# MAX3462.net
KiCad netlist of a schematic drawn in Altium Designer
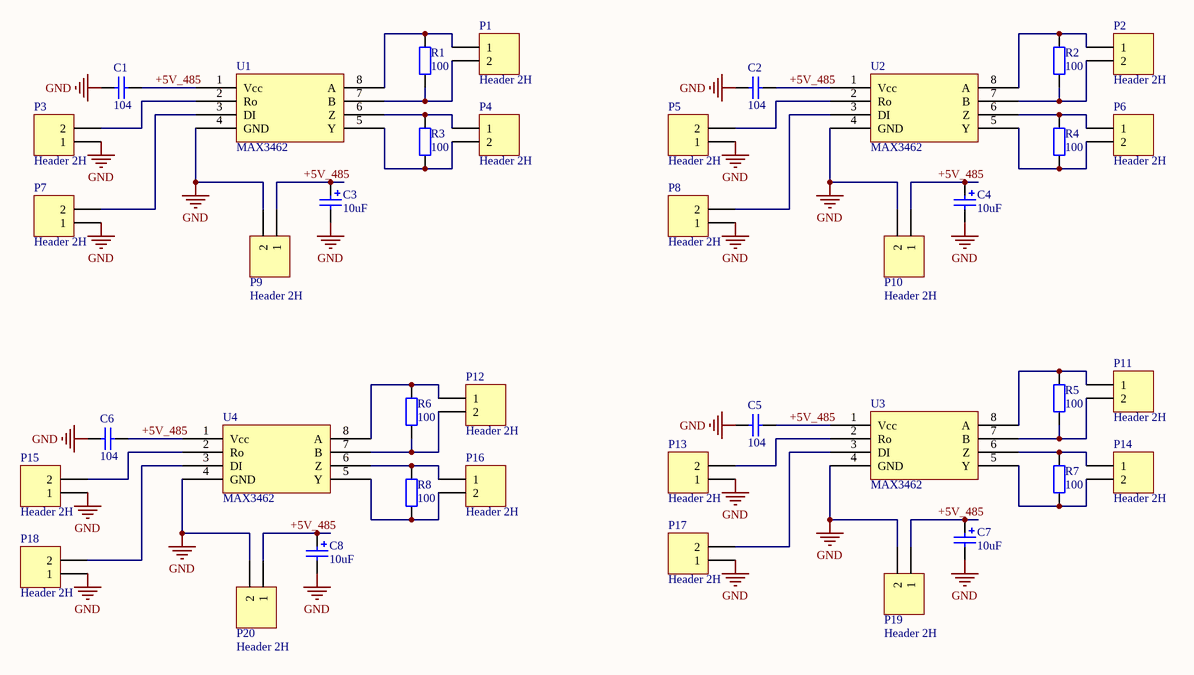
[diagram p0: MAX3462.SchDoc]

(export (version "E")
  (design (tool "Eeschema 10.0.6"))
  (components
    (comp (ref "C1")
      (value "104")
      (footprint "0805C")
      (description "Capacitor")
      (fields (field (name "PUBLISHER") "Altium Limited"))
      (libsource (lib "Miscellaneous Devices") (part "Cap"))
    )
    (comp (ref "C2")
      (value "104")
      (footprint "0805C")
      (description "Capacitor")
      (fields (field (name "PUBLISHER") "Altium Limited"))
      (libsource (lib "Miscellaneous Devices") (part "Cap"))
    )
    (comp (ref "C3")
      (value "10uF")
      (footprint "C68uF")
      (description "Polarized Capacitor (Axial)")
      (fields (field (name "PUBLISHER") "Altium Limited"))
      (libsource (lib "Miscellaneous Devices") (part "Cap Pol2"))
    )
    (comp (ref "C4")
      (value "10uF")
      (footprint "C68uF")
      (description "Polarized Capacitor (Axial)")
      (fields (field (name "PUBLISHER") "Altium Limited"))
      (libsource (lib "Miscellaneous Devices") (part "Cap Pol2"))
    )
    (comp (ref "C5")
      (value "104")
      (footprint "0805C")
      (description "Capacitor")
      (fields (field (name "PUBLISHER") "Altium Limited"))
      (libsource (lib "Miscellaneous Devices") (part "Cap"))
    )
    (comp (ref "C6")
      (value "104")
      (footprint "0805C")
      (description "Capacitor")
      (fields (field (name "PUBLISHER") "Altium Limited"))
      (libsource (lib "Miscellaneous Devices") (part "Cap"))
    )
    (comp (ref "C7")
      (value "10uF")
      (footprint "C68uF")
      (description "Polarized Capacitor (Axial)")
      (fields (field (name "PUBLISHER") "Altium Limited"))
      (libsource (lib "Miscellaneous Devices") (part "Cap Pol2"))
    )
    (comp (ref "C8")
      (value "10uF")
      (footprint "C68uF")
      (description "Polarized Capacitor (Axial)")
      (fields (field (name "PUBLISHER") "Altium Limited"))
      (libsource (lib "Miscellaneous Devices") (part "Cap Pol2"))
    )
    (comp (ref "P1")
      (value "Header 2H")
      (footprint "HDR1X2")
      (description "Header, 2-Pin, Right Angle")
      (fields (field (name "PUBLISHER") "Altium Limited"))
      (libsource (lib "Miscellaneous Connectors") (part "Header 2H"))
    )
    (comp (ref "P2")
      (value "Header 2H")
      (footprint "HDR1X2")
      (description "Header, 2-Pin, Right Angle")
      (fields (field (name "PUBLISHER") "Altium Limited"))
      (libsource (lib "Miscellaneous Connectors") (part "Header 2H"))
    )
    (comp (ref "P3")
      (value "Header 2H")
      (footprint "HDR1X2")
      (description "Header, 2-Pin, Right Angle")
      (fields (field (name "PUBLISHER") "Altium Limited"))
      (libsource (lib "") (part "Header 2H_2"))
    )
    (comp (ref "P4")
      (value "Header 2H")
      (footprint "HDR1X2")
      (description "Header, 2-Pin, Right Angle")
      (fields (field (name "PUBLISHER") "Altium Limited"))
      (libsource (lib "Miscellaneous Connectors") (part "Header 2H"))
    )
    (comp (ref "P5")
      (value "Header 2H")
      (footprint "HDR1X2")
      (description "Header, 2-Pin, Right Angle")
      (fields (field (name "PUBLISHER") "Altium Limited"))
      (libsource (lib "") (part "Header 2H_2"))
    )
    (comp (ref "P6")
      (value "Header 2H")
      (footprint "HDR1X2")
      (description "Header, 2-Pin, Right Angle")
      (fields (field (name "PUBLISHER") "Altium Limited"))
      (libsource (lib "Miscellaneous Connectors") (part "Header 2H"))
    )
    (comp (ref "P7")
      (value "Header 2H")
      (footprint "HDR1X2")
      (description "Header, 2-Pin, Right Angle")
      (fields (field (name "PUBLISHER") "Altium Limited"))
      (libsource (lib "") (part "Header 2H_2"))
    )
    (comp (ref "P8")
      (value "Header 2H")
      (footprint "HDR1X2")
      (description "Header, 2-Pin, Right Angle")
      (fields (field (name "PUBLISHER") "Altium Limited"))
      (libsource (lib "") (part "Header 2H_2"))
    )
    (comp (ref "P9")
      (value "Header 2H")
      (footprint "HDR1X2")
      (description "Header, 2-Pin, Right Angle")
      (fields (field (name "PUBLISHER") "Altium Limited"))
      (libsource (lib "") (part "Header 2H_1"))
    )
    (comp (ref "P10")
      (value "Header 2H")
      (footprint "HDR1X2")
      (description "Header, 2-Pin, Right Angle")
      (fields (field (name "PUBLISHER") "Altium Limited"))
      (libsource (lib "") (part "Header 2H_1"))
    )
    (comp (ref "P11")
      (value "Header 2H")
      (footprint "HDR1X2")
      (description "Header, 2-Pin, Right Angle")
      (fields (field (name "PUBLISHER") "Altium Limited"))
      (libsource (lib "Miscellaneous Connectors") (part "Header 2H"))
    )
    (comp (ref "P12")
      (value "Header 2H")
      (footprint "HDR1X2")
      (description "Header, 2-Pin, Right Angle")
      (fields (field (name "PUBLISHER") "Altium Limited"))
      (libsource (lib "Miscellaneous Connectors") (part "Header 2H"))
    )
    (comp (ref "P13")
      (value "Header 2H")
      (footprint "HDR1X2")
      (description "Header, 2-Pin, Right Angle")
      (fields (field (name "PUBLISHER") "Altium Limited"))
      (libsource (lib "") (part "Header 2H_2"))
    )
    (comp (ref "P14")
      (value "Header 2H")
      (footprint "HDR1X2")
      (description "Header, 2-Pin, Right Angle")
      (fields (field (name "PUBLISHER") "Altium Limited"))
      (libsource (lib "Miscellaneous Connectors") (part "Header 2H"))
    )
    (comp (ref "P15")
      (value "Header 2H")
      (footprint "HDR1X2")
      (description "Header, 2-Pin, Right Angle")
      (fields (field (name "PUBLISHER") "Altium Limited"))
      (libsource (lib "") (part "Header 2H_2"))
    )
    (comp (ref "P16")
      (value "Header 2H")
      (footprint "HDR1X2")
      (description "Header, 2-Pin, Right Angle")
      (fields (field (name "PUBLISHER") "Altium Limited"))
      (libsource (lib "Miscellaneous Connectors") (part "Header 2H"))
    )
    (comp (ref "P17")
      (value "Header 2H")
      (footprint "HDR1X2")
      (description "Header, 2-Pin, Right Angle")
      (fields (field (name "PUBLISHER") "Altium Limited"))
      (libsource (lib "") (part "Header 2H_2"))
    )
    (comp (ref "P18")
      (value "Header 2H")
      (footprint "HDR1X2")
      (description "Header, 2-Pin, Right Angle")
      (fields (field (name "PUBLISHER") "Altium Limited"))
      (libsource (lib "") (part "Header 2H_2"))
    )
    (comp (ref "P19")
      (value "Header 2H")
      (footprint "HDR1X2")
      (description "Header, 2-Pin, Right Angle")
      (fields (field (name "PUBLISHER") "Altium Limited"))
      (libsource (lib "") (part "Header 2H_1"))
    )
    (comp (ref "P20")
      (value "Header 2H")
      (footprint "HDR1X2")
      (description "Header, 2-Pin, Right Angle")
      (fields (field (name "PUBLISHER") "Altium Limited"))
      (libsource (lib "") (part "Header 2H_1"))
    )
    (comp (ref "R1")
      (value "100")
      (footprint "0805R")
      (description "Resistor")
      (fields (field (name "PUBLISHER") "Altium Limited"))
      (libsource (lib "Miscellaneous Devices") (part "Res2"))
    )
    (comp (ref "R2")
      (value "100")
      (footprint "0805R")
      (description "Resistor")
      (fields (field (name "PUBLISHER") "Altium Limited"))
      (libsource (lib "Miscellaneous Devices") (part "Res2"))
    )
    (comp (ref "R3")
      (value "100")
      (footprint "0805R")
      (description "Resistor")
      (fields (field (name "PUBLISHER") "Altium Limited"))
      (libsource (lib "Miscellaneous Devices") (part "Res2"))
    )
    (comp (ref "R4")
      (value "100")
      (footprint "0805R")
      (description "Resistor")
      (fields (field (name "PUBLISHER") "Altium Limited"))
      (libsource (lib "Miscellaneous Devices") (part "Res2"))
    )
    (comp (ref "R5")
      (value "100")
      (footprint "0805R")
      (description "Resistor")
      (fields (field (name "PUBLISHER") "Altium Limited"))
      (libsource (lib "Miscellaneous Devices") (part "Res2"))
    )
    (comp (ref "R6")
      (value "100")
      (footprint "0805R")
      (description "Resistor")
      (fields (field (name "PUBLISHER") "Altium Limited"))
      (libsource (lib "Miscellaneous Devices") (part "Res2"))
    )
    (comp (ref "R7")
      (value "100")
      (footprint "0805R")
      (description "Resistor")
      (fields (field (name "PUBLISHER") "Altium Limited"))
      (libsource (lib "Miscellaneous Devices") (part "Res2"))
    )
    (comp (ref "R8")
      (value "100")
      (footprint "0805R")
      (description "Resistor")
      (fields (field (name "PUBLISHER") "Altium Limited"))
      (libsource (lib "Miscellaneous Devices") (part "Res2"))
    )
    (comp (ref "U1") (value "MAX3462") (footprint "SO8") (libsource (lib "Schlib1") (part "MAX3462")))
    (comp (ref "U2") (value "MAX3462") (footprint "SO8") (libsource (lib "Schlib1") (part "MAX3462")))
    (comp (ref "U3") (value "MAX3462") (footprint "SO8") (libsource (lib "Schlib1") (part "MAX3462")))
    (comp (ref "U4") (value "MAX3462") (footprint "SO8") (libsource (lib "Schlib1") (part "MAX3462")))
  )
  (nets
    (net (code "1") (name "/+5V_485") (class "Default")
      (node (ref "C1") (pin "2") (pinfunction "2_2") (pintype "passive"))
      (node (ref "C2") (pin "2") (pinfunction "2_2") (pintype "passive"))
      (node (ref "C3") (pin "1") (pinfunction "1_1") (pintype "passive"))
      (node (ref "C4") (pin "1") (pinfunction "1_1") (pintype "passive"))
      (node (ref "C5") (pin "2") (pinfunction "2_2") (pintype "passive"))
      (node (ref "C6") (pin "2") (pinfunction "2_2") (pintype "passive"))
      (node (ref "C7") (pin "1") (pinfunction "1_1") (pintype "passive"))
      (node (ref "C8") (pin "1") (pinfunction "1_1") (pintype "passive"))
      (node (ref "P10") (pin "1") (pinfunction "1_1") (pintype "passive"))
      (node (ref "P19") (pin "1") (pinfunction "1_1") (pintype "passive"))
      (node (ref "P20") (pin "1") (pinfunction "1_1") (pintype "passive"))
      (node (ref "P9") (pin "1") (pinfunction "1_1") (pintype "passive"))
      (node (ref "U1") (pin "1") (pinfunction "Vcc_1") (pintype "passive"))
      (node (ref "U2") (pin "1") (pinfunction "Vcc_1") (pintype "passive"))
      (node (ref "U3") (pin "1") (pinfunction "Vcc_1") (pintype "passive"))
      (node (ref "U4") (pin "1") (pinfunction "Vcc_1") (pintype "passive"))
    )
    (net (code "2") (name "GND") (class "Default")
      (node (ref "C1") (pin "1") (pinfunction "1_1") (pintype "passive"))
      (node (ref "C2") (pin "1") (pinfunction "1_1") (pintype "passive"))
      (node (ref "C3") (pin "2") (pinfunction "2_2") (pintype "passive"))
      (node (ref "C4") (pin "2") (pinfunction "2_2") (pintype "passive"))
      (node (ref "C5") (pin "1") (pinfunction "1_1") (pintype "passive"))
      (node (ref "C6") (pin "1") (pinfunction "1_1") (pintype "passive"))
      (node (ref "C7") (pin "2") (pinfunction "2_2") (pintype "passive"))
      (node (ref "C8") (pin "2") (pinfunction "2_2") (pintype "passive"))
      (node (ref "P10") (pin "2") (pinfunction "2_2") (pintype "passive"))
      (node (ref "P13") (pin "1") (pinfunction "1_1") (pintype "passive"))
      (node (ref "P15") (pin "1") (pinfunction "1_1") (pintype "passive"))
      (node (ref "P17") (pin "1") (pinfunction "1_1") (pintype "passive"))
      (node (ref "P18") (pin "1") (pinfunction "1_1") (pintype "passive"))
      (node (ref "P19") (pin "2") (pinfunction "2_2") (pintype "passive"))
      (node (ref "P20") (pin "2") (pinfunction "2_2") (pintype "passive"))
      (node (ref "P3") (pin "1") (pinfunction "1_1") (pintype "passive"))
      (node (ref "P5") (pin "1") (pinfunction "1_1") (pintype "passive"))
      (node (ref "P7") (pin "1") (pinfunction "1_1") (pintype "passive"))
      (node (ref "P8") (pin "1") (pinfunction "1_1") (pintype "passive"))
      (node (ref "P9") (pin "2") (pinfunction "2_2") (pintype "passive"))
      (node (ref "U1") (pin "4") (pinfunction "GND_4") (pintype "passive"))
      (node (ref "U2") (pin "4") (pinfunction "GND_4") (pintype "passive"))
      (node (ref "U3") (pin "4") (pinfunction "GND_4") (pintype "passive"))
      (node (ref "U4") (pin "4") (pinfunction "GND_4") (pintype "passive"))
    )
    (net (code "3") (name "Net-(U1-A)") (class "Default")
      (node (ref "P1") (pin "1") (pinfunction "1_1") (pintype "passive"))
      (node (ref "R1") (pin "2") (pinfunction "2_2") (pintype "passive"))
      (node (ref "U1") (pin "8") (pinfunction "A_8") (pintype "passive"))
    )
    (net (code "4") (name "Net-(U1-B)") (class "Default")
      (node (ref "P1") (pin "2") (pinfunction "2_2") (pintype "passive"))
      (node (ref "R1") (pin "1") (pinfunction "1_1") (pintype "passive"))
      (node (ref "U1") (pin "7") (pinfunction "B_7") (pintype "passive"))
    )
    (net (code "5") (name "Net-(U1-DI)") (class "Default")
      (node (ref "P7") (pin "2") (pinfunction "2_2") (pintype "passive"))
      (node (ref "U1") (pin "3") (pinfunction "DI_3") (pintype "passive"))
    )
    (net (code "6") (name "Net-(U1-Ro)") (class "Default")
      (node (ref "P3") (pin "2") (pinfunction "2_2") (pintype "passive"))
      (node (ref "U1") (pin "2") (pinfunction "Ro_2") (pintype "passive"))
    )
    (net (code "7") (name "Net-(U1-Y)") (class "Default")
      (node (ref "P4") (pin "2") (pinfunction "2_2") (pintype "passive"))
      (node (ref "R3") (pin "1") (pinfunction "1_1") (pintype "passive"))
      (node (ref "U1") (pin "5") (pinfunction "Y_5") (pintype "passive"))
    )
    (net (code "8") (name "Net-(U1-Z)") (class "Default")
      (node (ref "P4") (pin "1") (pinfunction "1_1") (pintype "passive"))
      (node (ref "R3") (pin "2") (pinfunction "2_2") (pintype "passive"))
      (node (ref "U1") (pin "6") (pinfunction "Z_6") (pintype "passive"))
    )
    (net (code "9") (name "Net-(U2-A)") (class "Default")
      (node (ref "P2") (pin "1") (pinfunction "1_1") (pintype "passive"))
      (node (ref "R2") (pin "2") (pinfunction "2_2") (pintype "passive"))
      (node (ref "U2") (pin "8") (pinfunction "A_8") (pintype "passive"))
    )
    (net (code "10") (name "Net-(U2-B)") (class "Default")
      (node (ref "P2") (pin "2") (pinfunction "2_2") (pintype "passive"))
      (node (ref "R2") (pin "1") (pinfunction "1_1") (pintype "passive"))
      (node (ref "U2") (pin "7") (pinfunction "B_7") (pintype "passive"))
    )
    (net (code "11") (name "Net-(U2-DI)") (class "Default")
      (node (ref "P8") (pin "2") (pinfunction "2_2") (pintype "passive"))
      (node (ref "U2") (pin "3") (pinfunction "DI_3") (pintype "passive"))
    )
    (net (code "12") (name "Net-(U2-Ro)") (class "Default")
      (node (ref "P5") (pin "2") (pinfunction "2_2") (pintype "passive"))
      (node (ref "U2") (pin "2") (pinfunction "Ro_2") (pintype "passive"))
    )
    (net (code "13") (name "Net-(U2-Y)") (class "Default")
      (node (ref "P6") (pin "2") (pinfunction "2_2") (pintype "passive"))
      (node (ref "R4") (pin "1") (pinfunction "1_1") (pintype "passive"))
      (node (ref "U2") (pin "5") (pinfunction "Y_5") (pintype "passive"))
    )
    (net (code "14") (name "Net-(U2-Z)") (class "Default")
      (node (ref "P6") (pin "1") (pinfunction "1_1") (pintype "passive"))
      (node (ref "R4") (pin "2") (pinfunction "2_2") (pintype "passive"))
      (node (ref "U2") (pin "6") (pinfunction "Z_6") (pintype "passive"))
    )
    (net (code "15") (name "Net-(U3-A)") (class "Default")
      (node (ref "P11") (pin "1") (pinfunction "1_1") (pintype "passive"))
      (node (ref "R5") (pin "2") (pinfunction "2_2") (pintype "passive"))
      (node (ref "U3") (pin "8") (pinfunction "A_8") (pintype "passive"))
    )
    (net (code "16") (name "Net-(U3-B)") (class "Default")
      (node (ref "P11") (pin "2") (pinfunction "2_2") (pintype "passive"))
      (node (ref "R5") (pin "1") (pinfunction "1_1") (pintype "passive"))
      (node (ref "U3") (pin "7") (pinfunction "B_7") (pintype "passive"))
    )
    (net (code "17") (name "Net-(U3-DI)") (class "Default")
      (node (ref "P17") (pin "2") (pinfunction "2_2") (pintype "passive"))
      (node (ref "U3") (pin "3") (pinfunction "DI_3") (pintype "passive"))
    )
    (net (code "18") (name "Net-(U3-Ro)") (class "Default")
      (node (ref "P13") (pin "2") (pinfunction "2_2") (pintype "passive"))
      (node (ref "U3") (pin "2") (pinfunction "Ro_2") (pintype "passive"))
    )
    (net (code "19") (name "Net-(U3-Y)") (class "Default")
      (node (ref "P14") (pin "2") (pinfunction "2_2") (pintype "passive"))
      (node (ref "R7") (pin "1") (pinfunction "1_1") (pintype "passive"))
      (node (ref "U3") (pin "5") (pinfunction "Y_5") (pintype "passive"))
    )
    (net (code "20") (name "Net-(U3-Z)") (class "Default")
      (node (ref "P14") (pin "1") (pinfunction "1_1") (pintype "passive"))
      (node (ref "R7") (pin "2") (pinfunction "2_2") (pintype "passive"))
      (node (ref "U3") (pin "6") (pinfunction "Z_6") (pintype "passive"))
    )
    (net (code "21") (name "Net-(U4-A)") (class "Default")
      (node (ref "P12") (pin "1") (pinfunction "1_1") (pintype "passive"))
      (node (ref "R6") (pin "2") (pinfunction "2_2") (pintype "passive"))
      (node (ref "U4") (pin "8") (pinfunction "A_8") (pintype "passive"))
    )
    (net (code "22") (name "Net-(U4-B)") (class "Default")
      (node (ref "P12") (pin "2") (pinfunction "2_2") (pintype "passive"))
      (node (ref "R6") (pin "1") (pinfunction "1_1") (pintype "passive"))
      (node (ref "U4") (pin "7") (pinfunction "B_7") (pintype "passive"))
    )
    (net (code "23") (name "Net-(U4-DI)") (class "Default")
      (node (ref "P18") (pin "2") (pinfunction "2_2") (pintype "passive"))
      (node (ref "U4") (pin "3") (pinfunction "DI_3") (pintype "passive"))
    )
    (net (code "24") (name "Net-(U4-Ro)") (class "Default")
      (node (ref "P15") (pin "2") (pinfunction "2_2") (pintype "passive"))
      (node (ref "U4") (pin "2") (pinfunction "Ro_2") (pintype "passive"))
    )
    (net (code "25") (name "Net-(U4-Y)") (class "Default")
      (node (ref "P16") (pin "2") (pinfunction "2_2") (pintype "passive"))
      (node (ref "R8") (pin "1") (pinfunction "1_1") (pintype "passive"))
      (node (ref "U4") (pin "5") (pinfunction "Y_5") (pintype "passive"))
    )
    (net (code "26") (name "Net-(U4-Z)") (class "Default")
      (node (ref "P16") (pin "1") (pinfunction "1_1") (pintype "passive"))
      (node (ref "R8") (pin "2") (pinfunction "2_2") (pintype "passive"))
      (node (ref "U4") (pin "6") (pinfunction "Z_6") (pintype "passive"))
    )
  )
)
